# Transnavigators_Wheelchair_Schematic.net
KiCad netlist of a schematic drawn in EAGLE
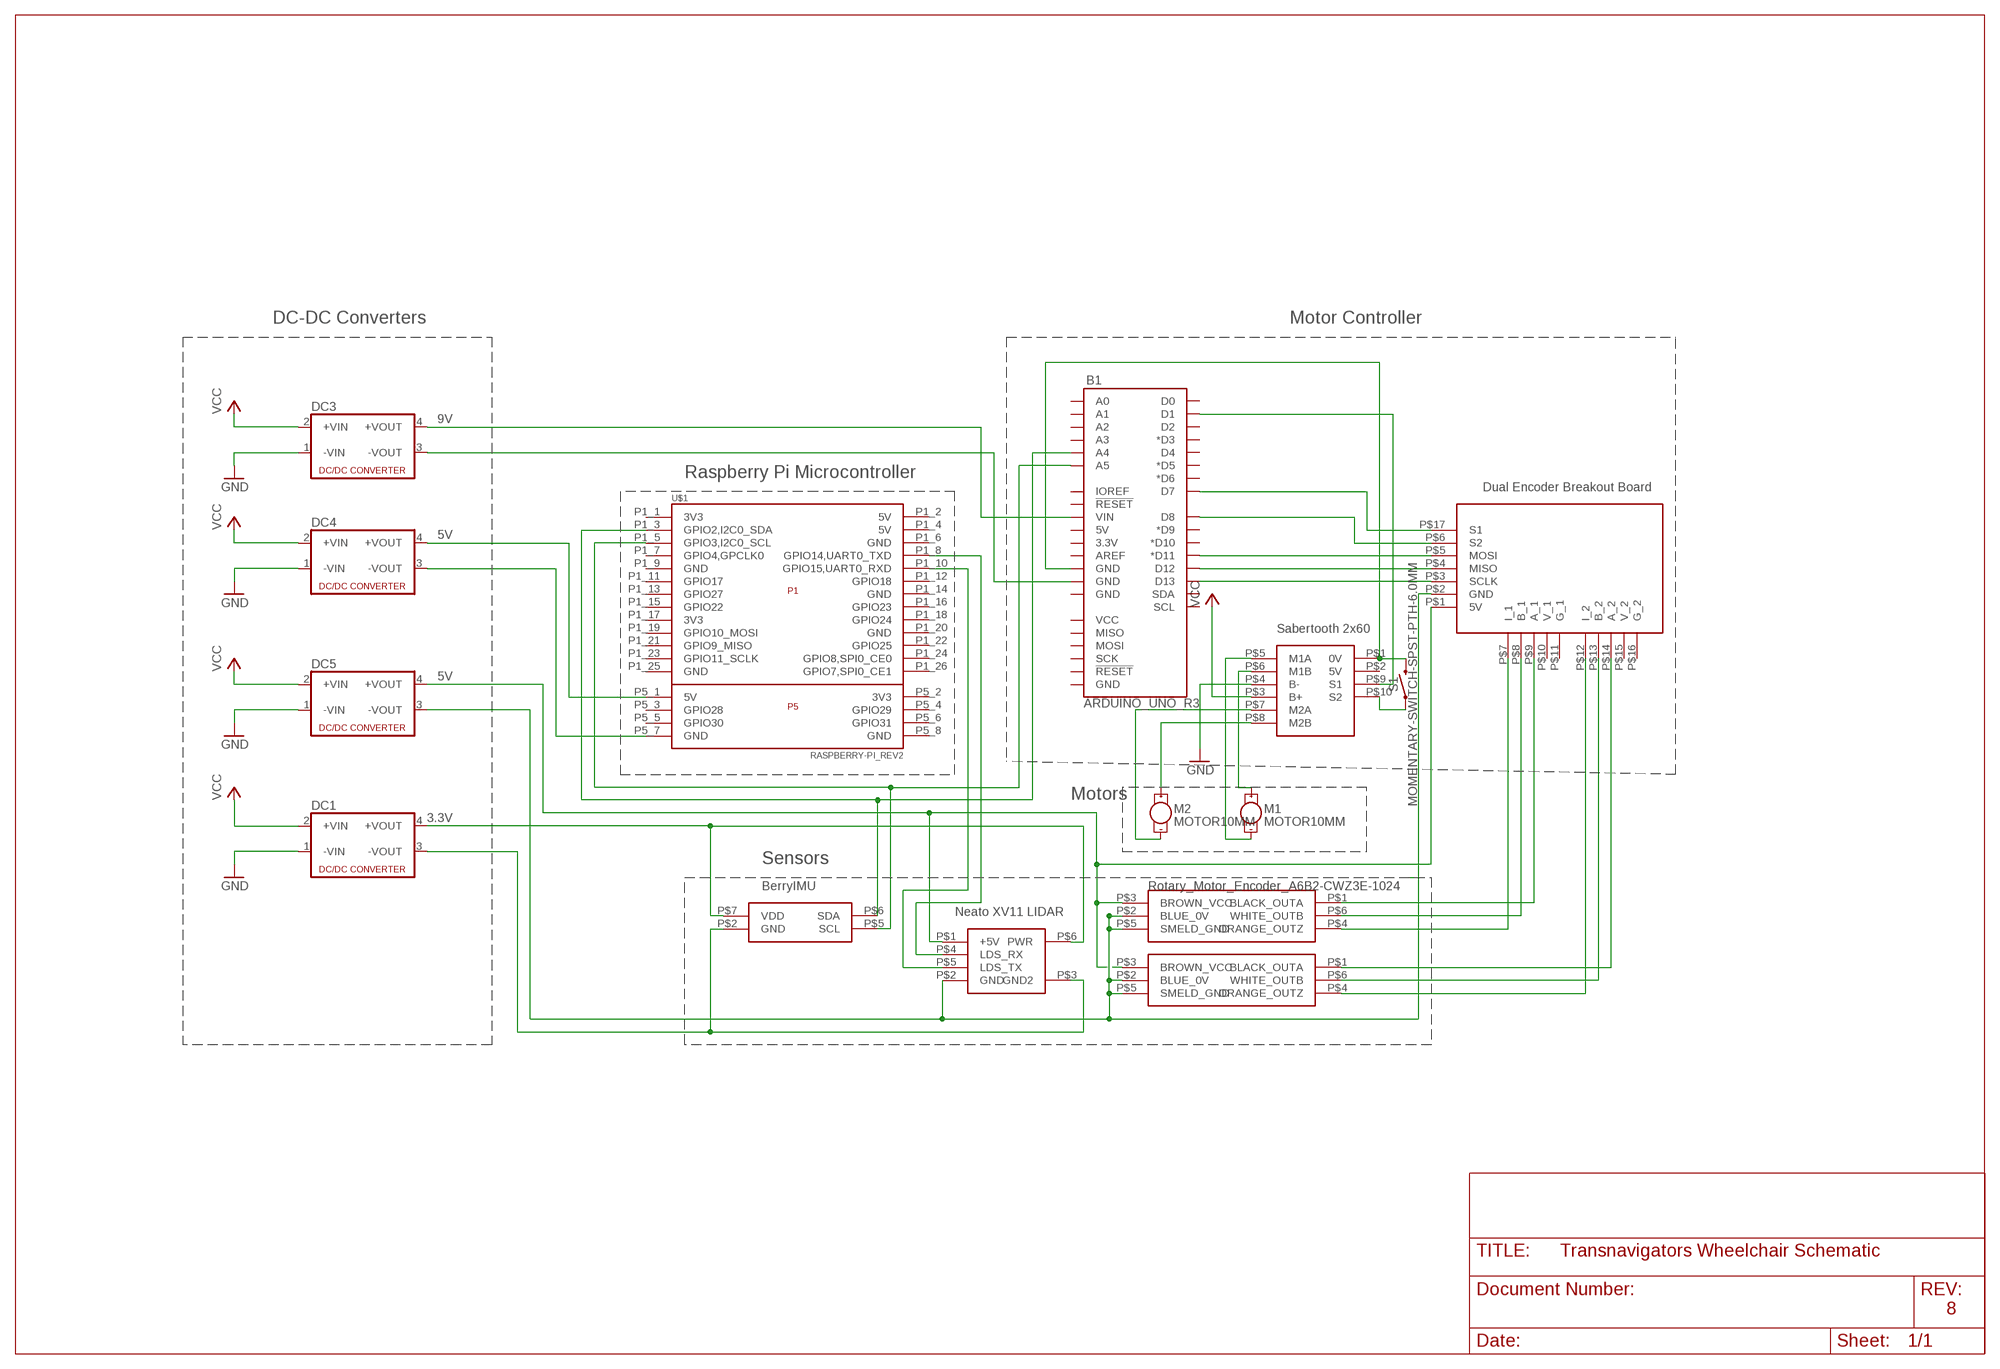
[diagram p0: schematic, sheet 1]

(export (version "E")
  (design (tool "Eeschema 10.0.6"))
  (components
    (comp (ref "B1")
      (value "ARDUINO_UNO_R3")
      (footprint "eagle-import:ARDUINO_R3")
      (libsource (lib "eagle-import") (part "ARDUINO_UNO_R3"))
    )
    (comp (ref "DC1")
      (value "NME")
      (footprint "eagle-import:NME")
      (fields (field (name "MF") "C & D TECHNOLOGIES, INC") (field (name "MPN") "NME1205D"))
      (libsource (lib "eagle-import") (part "NME"))
    )
    (comp (ref "DC3")
      (value "NME")
      (footprint "eagle-import:NME")
      (fields (field (name "MF") "C & D TECHNOLOGIES, INC") (field (name "MPN") "NME1205D"))
      (libsource (lib "eagle-import") (part "NME"))
    )
    (comp (ref "DC4")
      (value "NME")
      (footprint "eagle-import:NME")
      (fields (field (name "MF") "C & D TECHNOLOGIES, INC") (field (name "MPN") "NME1205D"))
      (libsource (lib "eagle-import") (part "NME"))
    )
    (comp (ref "DC5")
      (value "NME")
      (footprint "eagle-import:NME")
      (fields (field (name "MF") "C & D TECHNOLOGIES, INC") (field (name "MPN") "NME1205D"))
      (libsource (lib "eagle-import") (part "NME"))
    )
    (comp (ref "M1")
      (value "MOTOR10MM")
      (footprint "eagle-import:VIBE-MOTOR-10MM")
      (libsource (lib "eagle-import") (part "MOTOR10MM"))
    )
    (comp (ref "M2")
      (value "MOTOR10MM")
      (footprint "eagle-import:VIBE-MOTOR-10MM")
      (libsource (lib "eagle-import") (part "MOTOR10MM"))
    )
    (comp (ref "S1")
      (value "MOMENTARY-SWITCH-SPST-PTH-6.0MM")
      (footprint "eagle-import:TACTILE_SWITCH_PTH_6.0MM")
      (libsource (lib "eagle-import") (part "MOMENTARY-SWITCH-SPST-PTH-6.0MM"))
    )
    (comp (ref "U$1")
      (value "RASPBERRY-PI_REV2")
      (footprint "eagle-import:RASPBERRY-PI_REV2")
      (libsource (lib "eagle-import") (part "RASPBERRY-PI_REV2"))
    )
    (comp (ref "U$2")
      (value "ENCODER_A6B2")
      (footprint "eagle-import:ENCODER_A6B2")
      (libsource (lib "eagle-import") (part "ENCODER_A6B2"))
    )
    (comp (ref "U$3")
      (value "ENCODER_A6B2")
      (footprint "eagle-import:ENCODER_A6B2")
      (libsource (lib "eagle-import") (part "ENCODER_A6B2"))
    )
    (comp (ref "U$4")
      (value "BERRYIMU")
      (footprint "eagle-import:BERRYIMU")
      (libsource (lib "eagle-import") (part "BERRYIMU"))
    )
    (comp (ref "U$5")
      (value "DUAL_LS7366R")
      (footprint "eagle-import:DUAL_LS7366R")
      (libsource (lib "eagle-import") (part "DUAL_LS7366R"))
    )
    (comp (ref "U$6")
      (value "SABERTOOTH2X60")
      (footprint "eagle-import:SABERTOOTH2X60")
      (libsource (lib "eagle-import") (part "SABERTOOTH2X60"))
    )
    (comp (ref "XV11LIDAR")
      (value "XV11LIDAR")
      (footprint "eagle-import:LIDAR")
      (libsource (lib "eagle-import") (part "XV11LIDAR"))
    )
  )
  (nets
    (net (code "1") (name "GND") (class "Default")
      (node (ref "DC1") (pin "1") (pinfunction "-VIN_1") (pintype "passive"))
      (node (ref "DC3") (pin "1") (pinfunction "-VIN_1") (pintype "passive"))
      (node (ref "DC4") (pin "1") (pinfunction "-VIN_1") (pintype "passive"))
      (node (ref "DC5") (pin "1") (pinfunction "-VIN_1") (pintype "passive"))
      (node (ref "U$6") (pin "P$4") (pinfunction "B-_P$4") (pintype "bidirectional"))
    )
    (net (code "2") (name "Net-(B1-*D11)") (class "Default")
      (node (ref "B1") (pin "D11") (pinfunction "*D11_D11") (pintype "bidirectional"))
      (node (ref "U$5") (pin "P$5") (pinfunction "MOSI_P$5") (pintype "bidirectional"))
    )
    (net (code "3") (name "Net-(DC1-+VOUT)") (class "Default")
      (node (ref "DC1") (pin "4") (pinfunction "+VOUT_4") (pintype "passive"))
      (node (ref "U$4") (pin "P$7") (pinfunction "VDD_P$7") (pintype "bidirectional"))
      (node (ref "XV11LIDAR") (pin "P$6") (pinfunction "PWR_P$6") (pintype "bidirectional"))
    )
    (net (code "4") (name "Net-(DC1--VOUT)") (class "Default")
      (node (ref "DC1") (pin "3") (pinfunction "-VOUT_3") (pintype "passive"))
      (node (ref "U$4") (pin "P$2") (pinfunction "GND_P$2") (pintype "bidirectional"))
      (node (ref "XV11LIDAR") (pin "P$3") (pinfunction "GND2_P$3") (pintype "bidirectional"))
    )
    (net (code "5") (name "Net-(DC3-+VOUT)") (class "Default")
      (node (ref "B1") (pin "VIN") (pinfunction "VIN_VIN") (pintype "bidirectional"))
      (node (ref "DC3") (pin "4") (pinfunction "+VOUT_4") (pintype "passive"))
    )
    (net (code "6") (name "Net-(DC3--VOUT)") (class "Default")
      (node (ref "B1") (pin "GND@3") (pinfunction "GND_GND@3") (pintype "bidirectional"))
      (node (ref "DC3") (pin "3") (pinfunction "-VOUT_3") (pintype "passive"))
    )
    (net (code "7") (name "Net-(DC4-+VOUT)") (class "Default")
      (node (ref "DC4") (pin "4") (pinfunction "+VOUT_4") (pintype "passive"))
      (node (ref "U$1") (pin "P5_1") (pinfunction "5V_P5_1") (pintype "bidirectional"))
    )
    (net (code "8") (name "Net-(DC4--VOUT)") (class "Default")
      (node (ref "DC4") (pin "3") (pinfunction "-VOUT_3") (pintype "passive"))
      (node (ref "U$1") (pin "P5_7") (pinfunction "GND_P5_7") (pintype "bidirectional"))
    )
    (net (code "9") (name "Net-(DC5-+VOUT)") (class "Default")
      (node (ref "DC5") (pin "4") (pinfunction "+VOUT_4") (pintype "passive"))
      (node (ref "U$2") (pin "P$3") (pinfunction "BROWN_VCC_P$3") (pintype "bidirectional"))
      (node (ref "U$3") (pin "P$3") (pinfunction "BROWN_VCC_P$3") (pintype "bidirectional"))
      (node (ref "U$5") (pin "P$1") (pinfunction "5V_P$1") (pintype "bidirectional"))
      (node (ref "XV11LIDAR") (pin "P$1") (pinfunction "+5V_P$1") (pintype "bidirectional"))
    )
    (net (code "10") (name "Net-(DC5--VOUT)") (class "Default")
      (node (ref "DC5") (pin "3") (pinfunction "-VOUT_3") (pintype "passive"))
      (node (ref "U$2") (pin "P$2") (pinfunction "BLUE_0V_P$2") (pintype "bidirectional"))
      (node (ref "U$2") (pin "P$5") (pinfunction "SMELD_GND_P$5") (pintype "bidirectional"))
      (node (ref "U$3") (pin "P$2") (pinfunction "BLUE_0V_P$2") (pintype "bidirectional"))
      (node (ref "U$3") (pin "P$5") (pinfunction "SMELD_GND_P$5") (pintype "bidirectional"))
      (node (ref "U$5") (pin "P$2") (pinfunction "GND_P$2") (pintype "bidirectional"))
      (node (ref "XV11LIDAR") (pin "P$2") (pinfunction "GND_P$2") (pintype "bidirectional"))
    )
    (net (code "11") (name "Net-(S1-2)") (class "Default")
      (node (ref "B1") (pin "GND@4") (pinfunction "GND_GND@4") (pintype "bidirectional"))
      (node (ref "S1") (pin "3") (pinfunction "2_3") (pintype "passive"))
      (node (ref "U$6") (pin "P$1") (pinfunction "0V_P$1") (pintype "bidirectional"))
    )
    (net (code "12") (name "Net-(U$1-GPIO2,I2C0_SDA)") (class "Default")
      (node (ref "B1") (pin "A4") (pinfunction "A4_A4") (pintype "bidirectional"))
      (node (ref "U$1") (pin "P1_3") (pinfunction "GPIO2,I2C0_SDA_P1_3") (pintype "bidirectional"))
      (node (ref "U$4") (pin "P$6") (pinfunction "SDA_P$6") (pintype "bidirectional"))
    )
    (net (code "13") (name "Net-(U$1-GPIO3,I2C0_SCL)") (class "Default")
      (node (ref "B1") (pin "A5") (pinfunction "A5_A5") (pintype "bidirectional"))
      (node (ref "U$1") (pin "P1_5") (pinfunction "GPIO3,I2C0_SCL_P1_5") (pintype "bidirectional"))
      (node (ref "U$4") (pin "P$5") (pinfunction "SCL_P$5") (pintype "bidirectional"))
    )
    (net (code "14") (name "Net-(U$1-GPIO14,UART0_TXD)") (class "Default")
      (node (ref "U$1") (pin "P1_8") (pinfunction "GPIO14,UART0_TXD_P1_8") (pintype "bidirectional"))
      (node (ref "XV11LIDAR") (pin "P$4") (pinfunction "LDS_RX_P$4") (pintype "bidirectional"))
    )
    (net (code "15") (name "Net-(U$1-GPIO15,UART0_RXD)") (class "Default")
      (node (ref "U$1") (pin "P1_10") (pinfunction "GPIO15,UART0_RXD_P1_10") (pintype "bidirectional"))
      (node (ref "XV11LIDAR") (pin "P$5") (pinfunction "LDS_TX_P$5") (pintype "bidirectional"))
    )
    (net (code "16") (name "Net-(U$2-BLACK_OUTA)") (class "Default")
      (node (ref "U$2") (pin "P$1") (pinfunction "BLACK_OUTA_P$1") (pintype "bidirectional"))
      (node (ref "U$5") (pin "P$9") (pinfunction "A_1_P$9") (pintype "bidirectional"))
    )
    (net (code "17") (name "Net-(U$2-ORANGE_OUTZ)") (class "Default")
      (node (ref "U$2") (pin "P$4") (pinfunction "ORANGE_OUTZ_P$4") (pintype "bidirectional"))
      (node (ref "U$5") (pin "P$7") (pinfunction "I_1_P$7") (pintype "bidirectional"))
    )
    (net (code "18") (name "Net-(U$2-WHITE_OUTB)") (class "Default")
      (node (ref "U$2") (pin "P$6") (pinfunction "WHITE_OUTB_P$6") (pintype "bidirectional"))
      (node (ref "U$5") (pin "P$8") (pinfunction "B_1_P$8") (pintype "bidirectional"))
    )
    (net (code "19") (name "Net-(U$3-BLACK_OUTA)") (class "Default")
      (node (ref "U$3") (pin "P$1") (pinfunction "BLACK_OUTA_P$1") (pintype "bidirectional"))
      (node (ref "U$5") (pin "P$14") (pinfunction "A_2_P$14") (pintype "bidirectional"))
    )
    (net (code "20") (name "Net-(U$3-ORANGE_OUTZ)") (class "Default")
      (node (ref "U$3") (pin "P$4") (pinfunction "ORANGE_OUTZ_P$4") (pintype "bidirectional"))
      (node (ref "U$5") (pin "P$12") (pinfunction "I_2_P$12") (pintype "bidirectional"))
    )
    (net (code "21") (name "Net-(U$3-WHITE_OUTB)") (class "Default")
      (node (ref "U$3") (pin "P$6") (pinfunction "WHITE_OUTB_P$6") (pintype "bidirectional"))
      (node (ref "U$5") (pin "P$13") (pinfunction "B_2_P$13") (pintype "bidirectional"))
    )
    (net (code "22") (name "Net-(U$5-MISO)") (class "Default")
      (node (ref "B1") (pin "D12") (pinfunction "D12_D12") (pintype "bidirectional"))
      (node (ref "U$5") (pin "P$4") (pinfunction "MISO_P$4") (pintype "bidirectional"))
    )
    (net (code "23") (name "Net-(U$5-S1)") (class "Default")
      (node (ref "B1") (pin "D7") (pinfunction "D7_D7") (pintype "bidirectional"))
      (node (ref "U$5") (pin "P$17") (pinfunction "S1_P$17") (pintype "bidirectional"))
    )
    (net (code "24") (name "Net-(U$5-S2)") (class "Default")
      (node (ref "B1") (pin "D8") (pinfunction "D8_D8") (pintype "bidirectional"))
      (node (ref "U$5") (pin "P$6") (pinfunction "S2_P$6") (pintype "bidirectional"))
    )
    (net (code "25") (name "Net-(U$5-SCLK)") (class "Default")
      (node (ref "B1") (pin "D13") (pinfunction "D13_D13") (pintype "bidirectional"))
      (node (ref "U$5") (pin "P$3") (pinfunction "SCLK_P$3") (pintype "bidirectional"))
    )
    (net (code "26") (name "Net-(U$6-M1A)") (class "Default")
      (node (ref "M1") (pin "-") (pinfunction "-_-") (pintype "bidirectional"))
      (node (ref "U$6") (pin "P$5") (pinfunction "M1A_P$5") (pintype "bidirectional"))
    )
    (net (code "27") (name "Net-(U$6-M1B)") (class "Default")
      (node (ref "M1") (pin "+") (pinfunction "+_+") (pintype "bidirectional"))
      (node (ref "U$6") (pin "P$6") (pinfunction "M1B_P$6") (pintype "bidirectional"))
    )
    (net (code "28") (name "Net-(U$6-M2A)") (class "Default")
      (node (ref "M2") (pin "-") (pinfunction "-_-") (pintype "bidirectional"))
      (node (ref "U$6") (pin "P$7") (pinfunction "M2A_P$7") (pintype "bidirectional"))
    )
    (net (code "29") (name "Net-(U$6-M2B)") (class "Default")
      (node (ref "M2") (pin "+") (pinfunction "+_+") (pintype "bidirectional"))
      (node (ref "U$6") (pin "P$8") (pinfunction "M2B_P$8") (pintype "bidirectional"))
    )
    (net (code "30") (name "Net-(U$6-S1)") (class "Default")
      (node (ref "B1") (pin "D1") (pinfunction "D1_D1") (pintype "bidirectional"))
      (node (ref "U$6") (pin "P$9") (pinfunction "S1_P$9") (pintype "bidirectional"))
    )
    (net (code "31") (name "Net-(U$6-S2)") (class "Default")
      (node (ref "S1") (pin "1") (pinfunction "1_1") (pintype "passive"))
      (node (ref "U$6") (pin "P$10") (pinfunction "S2_P$10") (pintype "bidirectional"))
    )
    (net (code "32") (name "VCC") (class "Default")
      (node (ref "DC1") (pin "2") (pinfunction "+VIN_2") (pintype "passive"))
      (node (ref "DC3") (pin "2") (pinfunction "+VIN_2") (pintype "passive"))
      (node (ref "DC4") (pin "2") (pinfunction "+VIN_2") (pintype "passive"))
      (node (ref "DC5") (pin "2") (pinfunction "+VIN_2") (pintype "passive"))
      (node (ref "U$6") (pin "P$3") (pinfunction "B+_P$3") (pintype "bidirectional"))
    )
    (net (code "33") (name "unconnected-(B1-*D3-PadD3)") (class "Default")
      (node (ref "B1") (pin "D3") (pinfunction "*D3_D3") (pintype "bidirectional"))
    )
    (net (code "34") (name "unconnected-(B1-*D5-PadD5)") (class "Default")
      (node (ref "B1") (pin "D5") (pinfunction "*D5_D5") (pintype "bidirectional"))
    )
    (net (code "35") (name "unconnected-(B1-*D6-PadD6)") (class "Default")
      (node (ref "B1") (pin "D6") (pinfunction "*D6_D6") (pintype "bidirectional"))
    )
    (net (code "36") (name "unconnected-(B1-*D9-PadD9)") (class "Default")
      (node (ref "B1") (pin "D9") (pinfunction "*D9_D9") (pintype "bidirectional"))
    )
    (net (code "37") (name "unconnected-(B1-*D10-PadD10)") (class "Default")
      (node (ref "B1") (pin "D10") (pinfunction "*D10_D10") (pintype "bidirectional"))
    )
    (net (code "38") (name "unconnected-(B1-GND-PadGND@1)") (class "Default")
      (node (ref "B1") (pin "GND@1") (pinfunction "GND_GND@1") (pintype "bidirectional"))
    )
    (net (code "39") (name "unconnected-(B1-GND-PadGND@2)") (class "Default")
      (node (ref "B1") (pin "GND@2") (pinfunction "GND_GND@2") (pintype "bidirectional"))
    )
    (net (code "40") (name "unconnected-(B1-Pad3.3V)") (class "Default")
      (node (ref "B1") (pin "3.3V") (pinfunction "3.3V_3.3V") (pintype "bidirectional"))
    )
    (net (code "41") (name "unconnected-(B1-Pad5V)") (class "Default")
      (node (ref "B1") (pin "5V") (pinfunction "5V_5V") (pintype "bidirectional"))
    )
    (net (code "42") (name "unconnected-(B1-PadA0)") (class "Default")
      (node (ref "B1") (pin "A0") (pinfunction "A0_A0") (pintype "bidirectional"))
    )
    (net (code "43") (name "unconnected-(B1-PadA1)") (class "Default")
      (node (ref "B1") (pin "A1") (pinfunction "A1_A1") (pintype "bidirectional"))
    )
    (net (code "44") (name "unconnected-(B1-PadA2)") (class "Default")
      (node (ref "B1") (pin "A2") (pinfunction "A2_A2") (pintype "bidirectional"))
    )
    (net (code "45") (name "unconnected-(B1-PadA3)") (class "Default")
      (node (ref "B1") (pin "A3") (pinfunction "A3_A3") (pintype "bidirectional"))
    )
    (net (code "46") (name "unconnected-(B1-PadAREF)") (class "Default")
      (node (ref "B1") (pin "AREF") (pinfunction "AREF_AREF") (pintype "bidirectional"))
    )
    (net (code "47") (name "unconnected-(B1-PadD0)") (class "Default")
      (node (ref "B1") (pin "D0") (pinfunction "D0_D0") (pintype "bidirectional"))
    )
    (net (code "48") (name "unconnected-(B1-PadD2)") (class "Default")
      (node (ref "B1") (pin "D2") (pinfunction "D2_D2") (pintype "bidirectional"))
    )
    (net (code "49") (name "unconnected-(B1-PadD4)") (class "Default")
      (node (ref "B1") (pin "D4") (pinfunction "D4_D4") (pintype "bidirectional"))
    )
    (net (code "50") (name "unconnected-(B1-PadIOREF)") (class "Default")
      (node (ref "B1") (pin "IOREF") (pinfunction "IOREF_IOREF") (pintype "bidirectional"))
    )
    (net (code "51") (name "unconnected-(B1-PadMISO)") (class "Default")
      (node (ref "B1") (pin "MISO") (pinfunction "MISO_MISO") (pintype "bidirectional"))
    )
    (net (code "52") (name "unconnected-(B1-PadMOSI)") (class "Default")
      (node (ref "B1") (pin "MOSI") (pinfunction "MOSI_MOSI") (pintype "bidirectional"))
    )
    (net (code "53") (name "unconnected-(B1-PadSCK)") (class "Default")
      (node (ref "B1") (pin "SCK") (pinfunction "SCK_SCK") (pintype "bidirectional"))
    )
    (net (code "54") (name "unconnected-(B1-PadSCL)") (class "Default")
      (node (ref "B1") (pin "SCL") (pinfunction "SCL_SCL") (pintype "bidirectional"))
    )
    (net (code "55") (name "unconnected-(B1-PadSDA)") (class "Default")
      (node (ref "B1") (pin "SDA") (pinfunction "SDA_SDA") (pintype "bidirectional"))
    )
    (net (code "56") (name "unconnected-(B1-PadVCC)") (class "Default")
      (node (ref "B1") (pin "VCC") (pinfunction "VCC_VCC") (pintype "bidirectional"))
    )
    (net (code "57") (name "unconnected-(B1-~{RESET}-PadRESET@1)") (class "Default")
      (node (ref "B1") (pin "RESET@1") (pinfunction "~{RESET}_RESET@1") (pintype "bidirectional"))
    )
    (net (code "58") (name "unconnected-(B1-~{RESET}-PadRESET@2)") (class "Default")
      (node (ref "B1") (pin "RESET@2") (pinfunction "~{RESET}_RESET@2") (pintype "bidirectional"))
    )
    (net (code "59") (name "unconnected-(U$1-3V3-PadP1_1)") (class "Default")
      (node (ref "U$1") (pin "P1_1") (pinfunction "3V3_P1_1") (pintype "bidirectional"))
    )
    (net (code "60") (name "unconnected-(U$1-3V3-PadP1_17)") (class "Default")
      (node (ref "U$1") (pin "P1_17") (pinfunction "3V3_P1_17") (pintype "bidirectional"))
    )
    (net (code "61") (name "unconnected-(U$1-3V3-PadP5_2)") (class "Default")
      (node (ref "U$1") (pin "P5_2") (pinfunction "3V3_P5_2") (pintype "bidirectional"))
    )
    (net (code "62") (name "unconnected-(U$1-5V-PadP1_2)") (class "Default")
      (node (ref "U$1") (pin "P1_2") (pinfunction "5V_P1_2") (pintype "bidirectional"))
    )
    (net (code "63") (name "unconnected-(U$1-5V-PadP1_4)") (class "Default")
      (node (ref "U$1") (pin "P1_4") (pinfunction "5V_P1_4") (pintype "bidirectional"))
    )
    (net (code "64") (name "unconnected-(U$1-GND-PadP1_6)") (class "Default")
      (node (ref "U$1") (pin "P1_6") (pinfunction "GND_P1_6") (pintype "bidirectional"))
    )
    (net (code "65") (name "unconnected-(U$1-GND-PadP1_9)") (class "Default")
      (node (ref "U$1") (pin "P1_9") (pinfunction "GND_P1_9") (pintype "bidirectional"))
    )
    (net (code "66") (name "unconnected-(U$1-GND-PadP1_14)") (class "Default")
      (node (ref "U$1") (pin "P1_14") (pinfunction "GND_P1_14") (pintype "bidirectional"))
    )
    (net (code "67") (name "unconnected-(U$1-GND-PadP1_20)") (class "Default")
      (node (ref "U$1") (pin "P1_20") (pinfunction "GND_P1_20") (pintype "bidirectional"))
    )
    (net (code "68") (name "unconnected-(U$1-GND-PadP1_25)") (class "Default")
      (node (ref "U$1") (pin "P1_25") (pinfunction "GND_P1_25") (pintype "bidirectional"))
    )
    (net (code "69") (name "unconnected-(U$1-GND-PadP5_8)") (class "Default")
      (node (ref "U$1") (pin "P5_8") (pinfunction "GND_P5_8") (pintype "bidirectional"))
    )
    (net (code "70") (name "unconnected-(U$1-GPIO4,GPCLK0-PadP1_7)") (class "Default")
      (node (ref "U$1") (pin "P1_7") (pinfunction "GPIO4,GPCLK0_P1_7") (pintype "bidirectional"))
    )
    (net (code "71") (name "unconnected-(U$1-GPIO7,SPI0_CE1-PadP1_26)") (class "Default")
      (node (ref "U$1") (pin "P1_26") (pinfunction "GPIO7,SPI0_CE1_P1_26") (pintype "bidirectional"))
    )
    (net (code "72") (name "unconnected-(U$1-GPIO8,SPI0_CE0-PadP1_24)") (class "Default")
      (node (ref "U$1") (pin "P1_24") (pinfunction "GPIO8,SPI0_CE0_P1_24") (pintype "bidirectional"))
    )
    (net (code "73") (name "unconnected-(U$1-GPIO9_MISO-PadP1_21)") (class "Default")
      (node (ref "U$1") (pin "P1_21") (pinfunction "GPIO9_MISO_P1_21") (pintype "bidirectional"))
    )
    (net (code "74") (name "unconnected-(U$1-GPIO10_MOSI-PadP1_19)") (class "Default")
      (node (ref "U$1") (pin "P1_19") (pinfunction "GPIO10_MOSI_P1_19") (pintype "bidirectional"))
    )
    (net (code "75") (name "unconnected-(U$1-GPIO11_SCLK-PadP1_23)") (class "Default")
      (node (ref "U$1") (pin "P1_23") (pinfunction "GPIO11_SCLK_P1_23") (pintype "bidirectional"))
    )
    (net (code "76") (name "unconnected-(U$1-GPIO17-PadP1_11)") (class "Default")
      (node (ref "U$1") (pin "P1_11") (pinfunction "GPIO17_P1_11") (pintype "bidirectional"))
    )
    (net (code "77") (name "unconnected-(U$1-GPIO18-PadP1_12)") (class "Default")
      (node (ref "U$1") (pin "P1_12") (pinfunction "GPIO18_P1_12") (pintype "bidirectional"))
    )
    (net (code "78") (name "unconnected-(U$1-GPIO22-PadP1_15)") (class "Default")
      (node (ref "U$1") (pin "P1_15") (pinfunction "GPIO22_P1_15") (pintype "bidirectional"))
    )
    (net (code "79") (name "unconnected-(U$1-GPIO23-PadP1_16)") (class "Default")
      (node (ref "U$1") (pin "P1_16") (pinfunction "GPIO23_P1_16") (pintype "bidirectional"))
    )
    (net (code "80") (name "unconnected-(U$1-GPIO24-PadP1_18)") (class "Default")
      (node (ref "U$1") (pin "P1_18") (pinfunction "GPIO24_P1_18") (pintype "bidirectional"))
    )
    (net (code "81") (name "unconnected-(U$1-GPIO25-PadP1_22)") (class "Default")
      (node (ref "U$1") (pin "P1_22") (pinfunction "GPIO25_P1_22") (pintype "bidirectional"))
    )
    (net (code "82") (name "unconnected-(U$1-GPIO27-PadP1_13)") (class "Default")
      (node (ref "U$1") (pin "P1_13") (pinfunction "GPIO27_P1_13") (pintype "bidirectional"))
    )
    (net (code "83") (name "unconnected-(U$1-GPIO28-PadP5_3)") (class "Default")
      (node (ref "U$1") (pin "P5_3") (pinfunction "GPIO28_P5_3") (pintype "bidirectional"))
    )
    (net (code "84") (name "unconnected-(U$1-GPIO29-PadP5_4)") (class "Default")
      (node (ref "U$1") (pin "P5_4") (pinfunction "GPIO29_P5_4") (pintype "bidirectional"))
    )
    (net (code "85") (name "unconnected-(U$1-GPIO30-PadP5_5)") (class "Default")
      (node (ref "U$1") (pin "P5_5") (pinfunction "GPIO30_P5_5") (pintype "bidirectional"))
    )
    (net (code "86") (name "unconnected-(U$1-GPIO31-PadP5_6)") (class "Default")
      (node (ref "U$1") (pin "P5_6") (pinfunction "GPIO31_P5_6") (pintype "bidirectional"))
    )
    (net (code "87") (name "unconnected-(U$5-G_1-PadP$11)") (class "Default")
      (node (ref "U$5") (pin "P$11") (pinfunction "G_1_P$11") (pintype "bidirectional"))
    )
    (net (code "88") (name "unconnected-(U$5-G_2-PadP$16)") (class "Default")
      (node (ref "U$5") (pin "P$16") (pinfunction "G_2_P$16") (pintype "bidirectional"))
    )
    (net (code "89") (name "unconnected-(U$5-V_1-PadP$10)") (class "Default")
      (node (ref "U$5") (pin "P$10") (pinfunction "V_1_P$10") (pintype "bidirectional"))
    )
    (net (code "90") (name "unconnected-(U$5-V_2-PadP$15)") (class "Default")
      (node (ref "U$5") (pin "P$15") (pinfunction "V_2_P$15") (pintype "bidirectional"))
    )
    (net (code "91") (name "unconnected-(U$6-5V-PadP$2)") (class "Default")
      (node (ref "U$6") (pin "P$2") (pinfunction "5V_P$2") (pintype "bidirectional"))
    )
  )
)
